# clock14.net
KiCad netlist of a schematic drawn in EAGLE
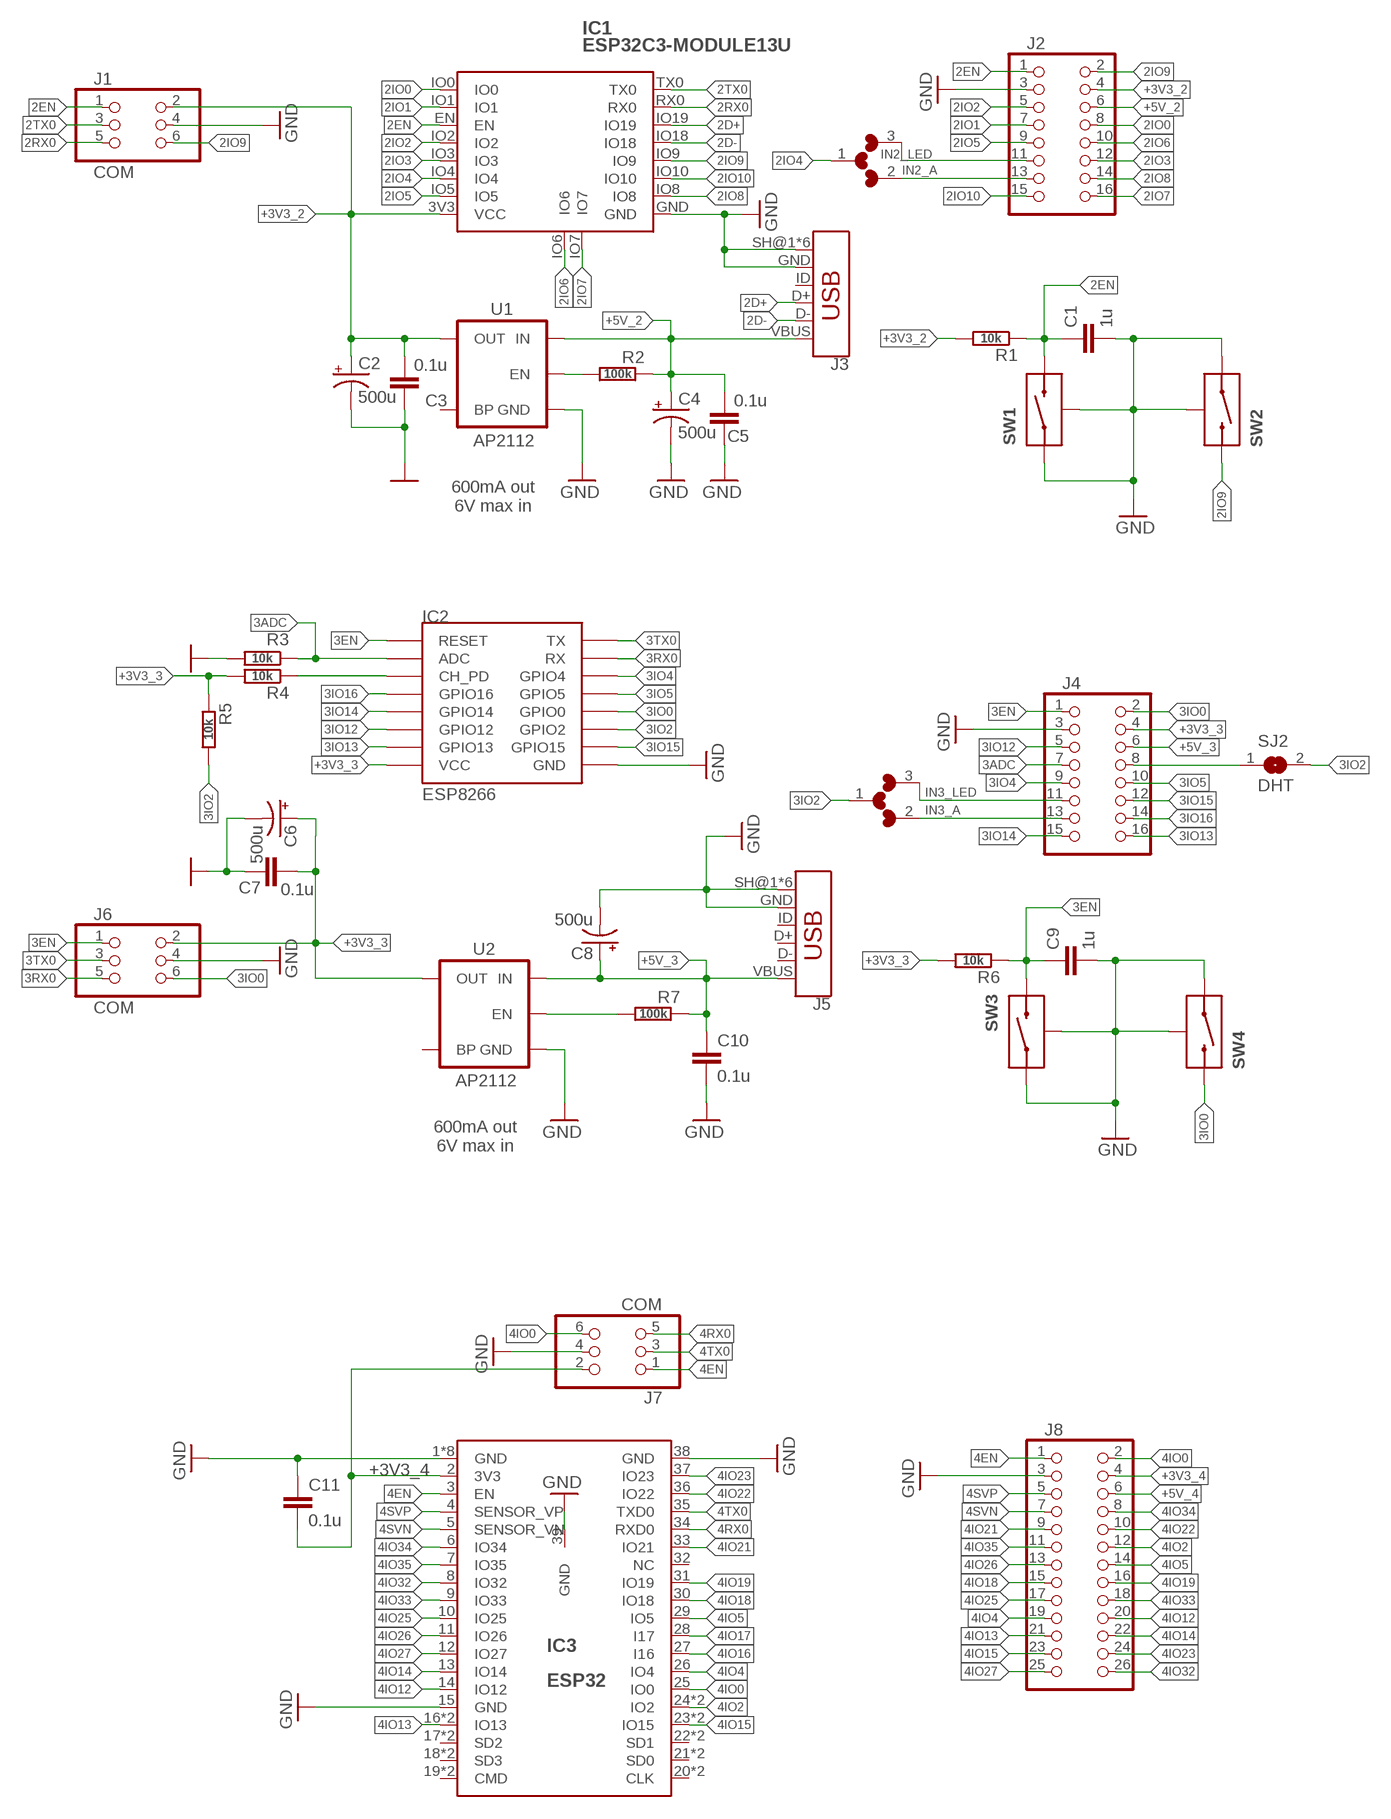
[diagram p0: schematic, sheet 1, part 1 of 2]
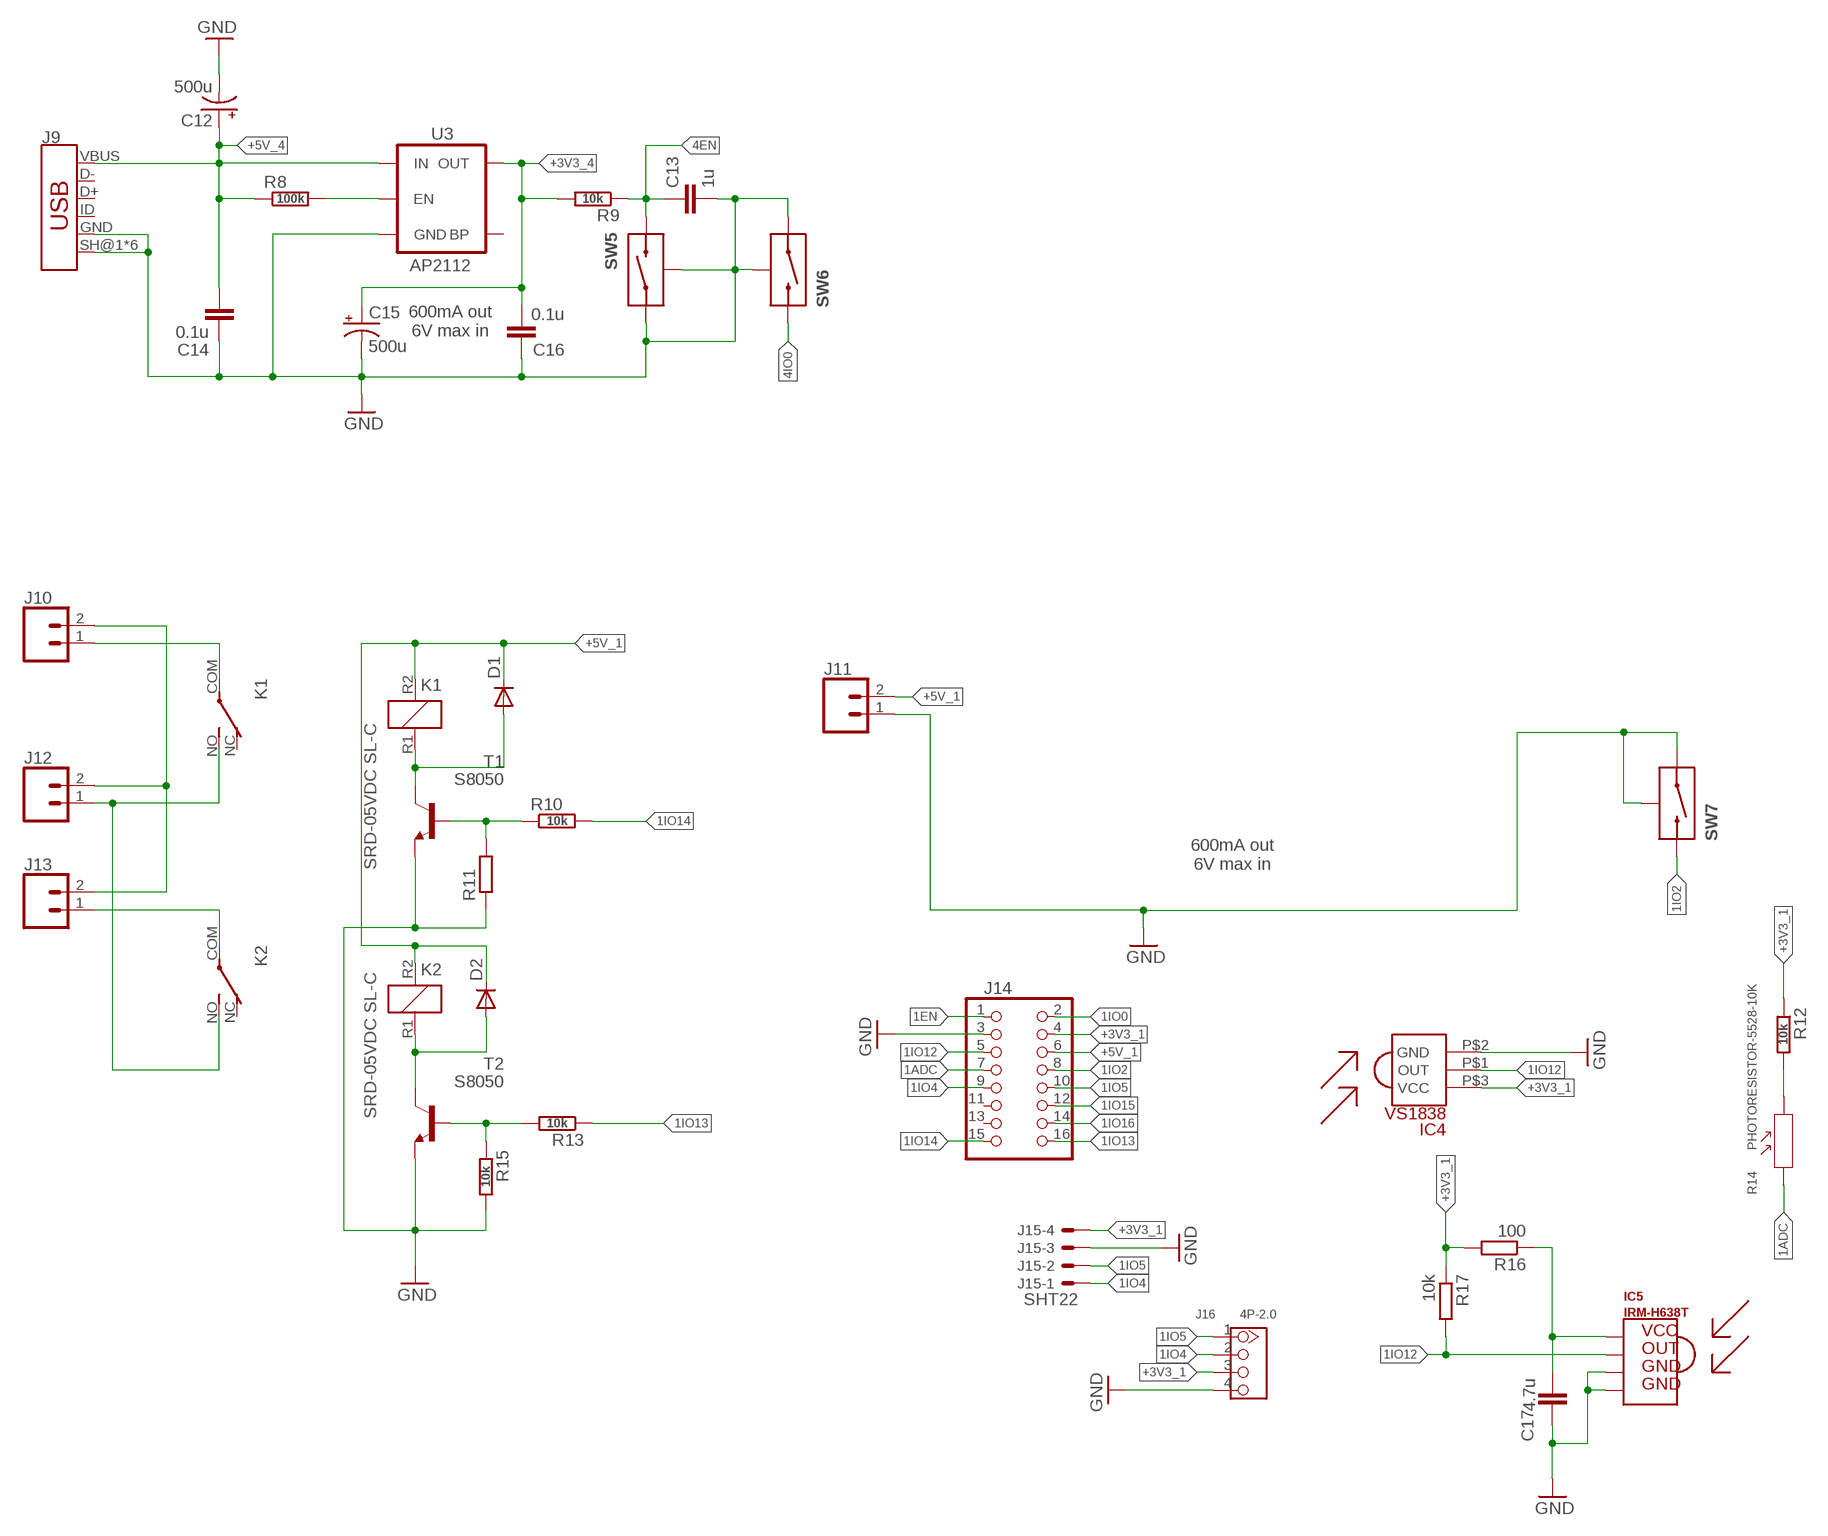
[diagram p1: schematic, sheet 1, part 2 of 2]

(export (version "E")
  (design (tool "Eeschema 10.0.6"))
  (components
    (comp (ref "C1")
      (value "1u")
      (footprint "eagle-import:0603-CAP")
      (libsource (lib "eagle-import") (part "CAP0603-CAP"))
    )
    (comp (ref "C2")
      (value "500u")
      (footprint "eagle-import:CPOL-RADIAL-100UF-25V")
      (libsource (lib "eagle-import") (part "CAP_POLPTH1"))
    )
    (comp (ref "C3")
      (value "0.1u")
      (footprint "eagle-import:0603-CAP")
      (libsource (lib "eagle-import") (part "CAP0603-CAP"))
    )
    (comp (ref "C4")
      (value "500u")
      (footprint "eagle-import:CPOL-RADIAL-100UF-25V")
      (libsource (lib "eagle-import") (part "CAP_POLPTH1"))
    )
    (comp (ref "C5")
      (value "0.1u")
      (footprint "eagle-import:0603-CAP")
      (libsource (lib "eagle-import") (part "CAP0603-CAP"))
    )
    (comp (ref "C6")
      (value "500u")
      (footprint "eagle-import:CPOL-RADIAL-100UF-25V")
      (libsource (lib "eagle-import") (part "CAP_POLPTH1"))
    )
    (comp (ref "C7")
      (value "0.1u")
      (footprint "eagle-import:0603-CAP")
      (libsource (lib "eagle-import") (part "CAP0603-CAP"))
    )
    (comp (ref "C8")
      (value "500u")
      (footprint "eagle-import:CPOL-RADIAL-100UF-25V")
      (libsource (lib "eagle-import") (part "CAP_POLPTH1"))
    )
    (comp (ref "C9")
      (value "1u")
      (footprint "eagle-import:0603-CAP")
      (libsource (lib "eagle-import") (part "CAP0603-CAP"))
    )
    (comp (ref "C10")
      (value "0.1u")
      (footprint "eagle-import:0603-CAP")
      (libsource (lib "eagle-import") (part "CAP0603-CAP"))
    )
    (comp (ref "C11")
      (value "0.1u")
      (footprint "eagle-import:0603-CAP")
      (libsource (lib "eagle-import") (part "CAP0603-CAP"))
    )
    (comp (ref "C12")
      (value "500u")
      (footprint "eagle-import:CPOL-RADIAL-100UF-25V")
      (libsource (lib "eagle-import") (part "CAP_POLPTH1"))
    )
    (comp (ref "C13")
      (value "1u")
      (footprint "eagle-import:0603-CAP")
      (libsource (lib "eagle-import") (part "CAP0603-CAP"))
    )
    (comp (ref "C14")
      (value "0.1u")
      (footprint "eagle-import:0603-CAP")
      (libsource (lib "eagle-import") (part "CAP0603-CAP"))
    )
    (comp (ref "C15")
      (value "500u")
      (footprint "eagle-import:CPOL-RADIAL-100UF-25V")
      (libsource (lib "eagle-import") (part "CAP_POLPTH1"))
    )
    (comp (ref "C16")
      (value "0.1u")
      (footprint "eagle-import:0603-CAP")
      (libsource (lib "eagle-import") (part "CAP0603-CAP"))
    )
    (comp (ref "C17")
      (value "4.7u")
      (footprint "eagle-import:0603-CAP")
      (libsource (lib "eagle-import") (part "CAP0603-CAP"))
    )
    (comp (ref "D1")
      (value "DIODE-SOD123")
      (footprint "eagle-import:SOD123")
      (libsource (lib "eagle-import") (part "DIODE-SOD123"))
    )
    (comp (ref "D2")
      (value "DIODE-SOD123")
      (footprint "eagle-import:SOD123")
      (libsource (lib "eagle-import") (part "DIODE-SOD123"))
    )
    (comp (ref "IC1")
      (value "ESP32C3-MODULE13U")
      (footprint "eagle-import:ESP32C3-13U")
      (libsource (lib "eagle-import") (part "ESP32C3-MODULE13U"))
    )
    (comp (ref "IC2")
      (value "ESP8266")
      (footprint "eagle-import:ESP12-SMD")
      (libsource (lib "eagle-import") (part "ESP12SMD"))
    )
    (comp (ref "IC3")
      (value "ESP32")
      (footprint "eagle-import:ESP32-WROOVER_WROOM")
      (libsource (lib "eagle-import") (part "ESP32-MODULEDUAL"))
    )
    (comp (ref "IC4")
      (value "VS1838")
      (footprint "eagle-import:IR")
      (libsource (lib "eagle-import") (part "VS1838"))
    )
    (comp (ref "IC5")
      (value "IRM-H638T")
      (footprint "eagle-import:IRM-H638T")
      (libsource (lib "eagle-import") (part "IRM-H638T"))
    )
    (comp (ref "J1")
      (value "COM")
      (footprint "eagle-import:2X03_SMT")
      (libsource (lib "eagle-import") (part "HEADER-2X3SMT"))
    )
    (comp (ref "J2")
      (value "HEADER-2X8")
      (footprint "eagle-import:2X8")
      (libsource (lib "eagle-import") (part "HEADER-2X8"))
    )
    (comp (ref "J3")
      (value "USB_MICRO-BFEMALE_SMT_")
      (footprint "eagle-import:USB-B-MICRO-SMD_MY")
      (libsource (lib "eagle-import") (part "USB_MICRO-BFEMALE_SMT_"))
    )
    (comp (ref "J4")
      (value "HEADER-2X8")
      (footprint "eagle-import:2X8")
      (libsource (lib "eagle-import") (part "HEADER-2X8"))
    )
    (comp (ref "J5")
      (value "USB_MICRO-BFEMALE_SMT_")
      (footprint "eagle-import:USB-B-MICRO-SMD_MY")
      (libsource (lib "eagle-import") (part "USB_MICRO-BFEMALE_SMT_"))
    )
    (comp (ref "J6")
      (value "COM")
      (footprint "eagle-import:2X03_SMT")
      (libsource (lib "eagle-import") (part "HEADER-2X3SMT"))
    )
    (comp (ref "J7")
      (value "COM")
      (footprint "eagle-import:2X03_SMT")
      (libsource (lib "eagle-import") (part "HEADER-2X3SMT"))
    )
    (comp (ref "J8")
      (value "HEADER-2X13")
      (footprint "eagle-import:2X13")
      (libsource (lib "eagle-import") (part "HEADER-2X13"))
    )
    (comp (ref "J9")
      (value "USB_MICRO-BFEMALE_SMT_")
      (footprint "eagle-import:USB-B-MICRO-SMD_MY")
      (libsource (lib "eagle-import") (part "USB_MICRO-BFEMALE_SMT_"))
    )
    (comp (ref "J10")
      (value "CONN_02")
      (footprint "eagle-import:1X02")
      (libsource (lib "eagle-import") (part "CONN_02"))
    )
    (comp (ref "J11")
      (value "CONN_02")
      (footprint "eagle-import:1X02")
      (libsource (lib "eagle-import") (part "CONN_02"))
    )
    (comp (ref "J12")
      (value "CONN_02")
      (footprint "eagle-import:1X02")
      (libsource (lib "eagle-import") (part "CONN_02"))
    )
    (comp (ref "J13")
      (value "CONN_02")
      (footprint "eagle-import:1X02")
      (libsource (lib "eagle-import") (part "CONN_02"))
    )
    (comp (ref "J14")
      (value "HEADER-2X8")
      (footprint "eagle-import:2X8")
      (libsource (lib "eagle-import") (part "HEADER-2X8"))
    )
    (comp (ref "J15")
      (value "SHT22")
      (footprint "eagle-import:70543-04")
      (libsource (lib "eagle-import") (part "C-GRID-04-70543"))
    )
    (comp (ref "J16")
      (value "4P-2.0")
      (footprint "eagle-import:HW4-2.0")
      (libsource (lib "eagle-import") (part "GROVE-CONNECTOR-DIP(4P-2.0)"))
    )
    (comp (ref "K1")
      (value "SRD-05VDC SL-C")
      (footprint "eagle-import:SL-C")
      (fields (field (name "MF") "AROMAT/ MATSUSHITA") (field (name "MPN") "CB1A-P-12V"))
      (libsource (lib "eagle-import") (part "CB1A-P-12V"))
    )
    (comp (ref "K2")
      (value "SRD-05VDC SL-C")
      (footprint "eagle-import:SL-C")
      (fields (field (name "MF") "AROMAT/ MATSUSHITA") (field (name "MPN") "CB1A-P-12V"))
      (libsource (lib "eagle-import") (part "CB1A-P-12V"))
    )
    (comp (ref "R1")
      (value "10k")
      (footprint "eagle-import:R0603")
      (libsource (lib "eagle-import") (part "R-EU_R0603"))
    )
    (comp (ref "R2")
      (value "100k")
      (footprint "eagle-import:R0603")
      (libsource (lib "eagle-import") (part "R-EU_R0603"))
    )
    (comp (ref "R3")
      (value "10k")
      (footprint "eagle-import:R0603")
      (libsource (lib "eagle-import") (part "R-EU_R0603"))
    )
    (comp (ref "R4")
      (value "10k")
      (footprint "eagle-import:R0603")
      (libsource (lib "eagle-import") (part "R-EU_R0603"))
    )
    (comp (ref "R5")
      (value "10k")
      (footprint "eagle-import:R0603")
      (libsource (lib "eagle-import") (part "R-EU_R0603"))
    )
    (comp (ref "R6")
      (value "10k")
      (footprint "eagle-import:R0603")
      (libsource (lib "eagle-import") (part "R-EU_R0603"))
    )
    (comp (ref "R7")
      (value "100k")
      (footprint "eagle-import:R0603")
      (libsource (lib "eagle-import") (part "R-EU_R0603"))
    )
    (comp (ref "R8")
      (value "100k")
      (footprint "eagle-import:R0603")
      (libsource (lib "eagle-import") (part "R-EU_R0603"))
    )
    (comp (ref "R9")
      (value "10k")
      (footprint "eagle-import:R0603")
      (libsource (lib "eagle-import") (part "R-EU_R0603"))
    )
    (comp (ref "R10")
      (value "10k")
      (footprint "eagle-import:R0603")
      (libsource (lib "eagle-import") (part "R-EU_R0603"))
    )
    (comp (ref "R11")
      (value "R-EU_R0603")
      (footprint "eagle-import:R0603")
      (libsource (lib "eagle-import") (part "R-EU_R0603"))
    )
    (comp (ref "R12")
      (value "10k")
      (footprint "eagle-import:R0603")
      (libsource (lib "eagle-import") (part "R-EU_R0603"))
    )
    (comp (ref "R13")
      (value "10k")
      (footprint "eagle-import:R0603")
      (libsource (lib "eagle-import") (part "R-EU_R0603"))
    )
    (comp (ref "R14")
      (value "PHOTORESISTOR-5528-10K")
      (footprint "eagle-import:SNR2-3.0")
      (libsource (lib "eagle-import") (part "PHOTORESISTOR-5528-10K(2P-5.0X4.2MM)"))
    )
    (comp (ref "R15")
      (value "10k")
      (footprint "eagle-import:R0603")
      (libsource (lib "eagle-import") (part "R-EU_R0603"))
    )
    (comp (ref "R16")
      (value "100")
      (footprint "eagle-import:R0603")
      (libsource (lib "eagle-import") (part "R-EU_R0603"))
    )
    (comp (ref "R17")
      (value "10k")
      (footprint "eagle-import:R0603")
      (libsource (lib "eagle-import") (part "R-EU_R0603"))
    )
    (comp (ref "SJ1")
      (value "L/W")
      (footprint "eagle-import:MICROBUILDER_SOLDERJUMPER_ARROW_NOPASTE_3")
      (libsource (lib "eagle-import") (part "MICROBUILDER_SOLDERJUMPER3"))
    )
    (comp (ref "SJ2")
      (value "DHT")
      (footprint "eagle-import:MICROBUILDER_SOLDERJUMPER_ARROW_NOPASTE")
      (libsource (lib "eagle-import") (part "MICROBUILDER_SOLDERJUMPER"))
    )
    (comp (ref "SJ3")
      (value "L/W")
      (footprint "eagle-import:MICROBUILDER_SOLDERJUMPER_ARROW_NOPASTE_3")
      (libsource (lib "eagle-import") (part "MICROBUILDER_SOLDERJUMPER3"))
    )
    (comp (ref "SW1")
      (value "RST")
      (footprint "eagle-import:MICROPUSH-BUT_TOP")
      (libsource (lib "eagle-import") (part "MICROSWITCH-BUTTON"))
    )
    (comp (ref "SW2")
      (value "PRG")
      (footprint "eagle-import:MICROPUSH-BUT_TOP")
      (libsource (lib "eagle-import") (part "MICROSWITCH-BUTTON"))
    )
    (comp (ref "SW3")
      (value "RST")
      (footprint "eagle-import:MICROPUSH-BUT_TOP")
      (libsource (lib "eagle-import") (part "MICROSWITCH-BUTTON"))
    )
    (comp (ref "SW4")
      (value "PRG")
      (footprint "eagle-import:MICROPUSH-BUT_TOP")
      (libsource (lib "eagle-import") (part "MICROSWITCH-BUTTON"))
    )
    (comp (ref "SW5")
      (value "RST")
      (footprint "eagle-import:MICROPUSH-BUT_TOP")
      (libsource (lib "eagle-import") (part "MICROSWITCH-BUTTON"))
    )
    (comp (ref "SW6")
      (value "PRG")
      (footprint "eagle-import:MICROPUSH-BUT_TOP")
      (libsource (lib "eagle-import") (part "MICROSWITCH-BUTTON"))
    )
    (comp (ref "SW7")
      (value "PRG")
      (footprint "eagle-import:MICROPUSH-BUT_TOP")
      (libsource (lib "eagle-import") (part "MICROSWITCH-BUTTON"))
    )
    (comp (ref "T1")
      (value "S8050")
      (footprint "eagle-import:SOT23-EBC")
      (libsource (lib "eagle-import") (part "-NPN-SOT23-EBC"))
    )
    (comp (ref "T2")
      (value "S8050")
      (footprint "eagle-import:SOT23-EBC")
      (libsource (lib "eagle-import") (part "-NPN-SOT23-EBC"))
    )
    (comp (ref "U1")
      (value "AP2112")
      (footprint "eagle-import:SOT23-5")
      (libsource (lib "eagle-import") (part "V_REG_LDOSMD"))
    )
    (comp (ref "U2")
      (value "AP2112")
      (footprint "eagle-import:SOT23-5")
      (libsource (lib "eagle-import") (part "V_REG_LDOSMD"))
    )
    (comp (ref "U3")
      (value "AP2112")
      (footprint "eagle-import:SOT23-5")
      (libsource (lib "eagle-import") (part "V_REG_LDOSMD"))
    )
  )
  (nets
    (net (code "1") (name "+3V3_1") (class "Default")
      (node (ref "IC4") (pin "P$3") (pinfunction "VCC_P$3") (pintype "bidirectional"))
      (node (ref "J14") (pin "4") (pinfunction "4_4") (pintype "passive"))
      (node (ref "J15") (pin "4") (pinfunction "S_4") (pintype "passive"))
      (node (ref "J16") (pin "3") (pinfunction "3_3") (pintype "bidirectional"))
      (node (ref "R12") (pin "1") (pinfunction "1_1") (pintype "passive"))
      (node (ref "R16") (pin "2") (pinfunction "2_2") (pintype "passive"))
      (node (ref "R17") (pin "1") (pinfunction "1_1") (pintype "passive"))
    )
    (net (code "2") (name "+3V3_2") (class "Default")
      (node (ref "C2") (pin "1") (pinfunction "+_1") (pintype "passive"))
      (node (ref "C3") (pin "2") (pinfunction "2_2") (pintype "passive"))
      (node (ref "IC1") (pin "3V3") (pinfunction "VCC_3V3") (pintype "power_in"))
      (node (ref "J1") (pin "2") (pinfunction "2_2") (pintype "passive"))
      (node (ref "J2") (pin "4") (pinfunction "4_4") (pintype "passive"))
      (node (ref "R1") (pin "2") (pinfunction "2_2") (pintype "passive"))
      (node (ref "U1") (pin "5") (pinfunction "OUT_5") (pintype "passive"))
    )
    (net (code "3") (name "+3V3_3") (class "Default")
      (node (ref "C6") (pin "1") (pinfunction "+_1") (pintype "passive"))
      (node (ref "C7") (pin "2") (pinfunction "2_2") (pintype "passive"))
      (node (ref "IC2") (pin "VCC") (pinfunction "VCC_VCC") (pintype "bidirectional"))
      (node (ref "J4") (pin "4") (pinfunction "4_4") (pintype "passive"))
      (node (ref "J6") (pin "2") (pinfunction "2_2") (pintype "passive"))
      (node (ref "R4") (pin "2") (pinfunction "2_2") (pintype "passive"))
      (node (ref "R5") (pin "1") (pinfunction "1_1") (pintype "passive"))
      (node (ref "R6") (pin "2") (pinfunction "2_2") (pintype "passive"))
      (node (ref "U2") (pin "5") (pinfunction "OUT_5") (pintype "passive"))
    )
    (net (code "4") (name "+3V3_4") (class "Default")
      (node (ref "C11") (pin "2") (pinfunction "2_2") (pintype "passive"))
      (node (ref "C15") (pin "1") (pinfunction "+_1") (pintype "passive"))
      (node (ref "C16") (pin "2") (pinfunction "2_2") (pintype "passive"))
      (node (ref "IC3") (pin "2") (pinfunction "3V3_2") (pintype "power_in"))
      (node (ref "J7") (pin "2") (pinfunction "2_2") (pintype "passive"))
      (node (ref "J8") (pin "4") (pinfunction "4_4") (pintype "passive"))
      (node (ref "R9") (pin "2") (pinfunction "2_2") (pintype "passive"))
      (node (ref "U3") (pin "5") (pinfunction "OUT_5") (pintype "passive"))
    )
    (net (code "5") (name "+5V_1") (class "Default")
      (node (ref "D1") (pin "C") (pinfunction "C_C") (pintype "passive"))
      (node (ref "D2") (pin "C") (pinfunction "C_C") (pintype "passive"))
      (node (ref "J11") (pin "2") (pinfunction "2_2") (pintype "passive"))
      (node (ref "J14") (pin "6") (pinfunction "6_6") (pintype "passive"))
      (node (ref "K1") (pin "R2") (pinfunction "2_R2") (pintype "passive"))
      (node (ref "K2") (pin "R2") (pinfunction "2_R2") (pintype "passive"))
    )
    (net (code "6") (name "+5V_2") (class "Default")
      (node (ref "C4") (pin "1") (pinfunction "+_1") (pintype "passive"))
      (node (ref "C5") (pin "2") (pinfunction "2_2") (pintype "passive"))
      (node (ref "J2") (pin "6") (pinfunction "6_6") (pintype "passive"))
      (node (ref "J3") (pin "VBUS") (pinfunction "VBUS_VBUS") (pintype "power_in"))
      (node (ref "R2") (pin "1") (pinfunction "1_1") (pintype "passive"))
      (node (ref "U1") (pin "1") (pinfunction "IN_1") (pintype "input"))
    )
    (net (code "7") (name "+5V_3") (class "Default")
      (node (ref "C10") (pin "1") (pinfunction "1_1") (pintype "passive"))
      (node (ref "C8") (pin "1") (pinfunction "+_1") (pintype "passive"))
      (node (ref "J4") (pin "6") (pinfunction "6_6") (pintype "passive"))
      (node (ref "J5") (pin "VBUS") (pinfunction "VBUS_VBUS") (pintype "power_in"))
      (node (ref "R7") (pin "1") (pinfunction "1_1") (pintype "passive"))
      (node (ref "U2") (pin "1") (pinfunction "IN_1") (pintype "input"))
    )
    (net (code "8") (name "+5V_4") (class "Default")
      (node (ref "C12") (pin "1") (pinfunction "+_1") (pintype "passive"))
      (node (ref "C14") (pin "1") (pinfunction "1_1") (pintype "passive"))
      (node (ref "J8") (pin "6") (pinfunction "6_6") (pintype "passive"))
      (node (ref "J9") (pin "VBUS") (pinfunction "VBUS_VBUS") (pintype "power_in"))
      (node (ref "R8") (pin "1") (pinfunction "1_1") (pintype "passive"))
      (node (ref "U3") (pin "1") (pinfunction "IN_1") (pintype "input"))
    )
    (net (code "9") (name "/IN2_A") (class "Default")
      (node (ref "J2") (pin "13") (pinfunction "13_13") (pintype "passive"))
      (node (ref "SJ1") (pin "2") (pinfunction "2_2") (pintype "passive"))
    )
    (net (code "10") (name "/IN2_LED") (class "Default")
      (node (ref "J2") (pin "11") (pinfunction "11_11") (pintype "passive"))
      (node (ref "SJ1") (pin "3") (pinfunction "3_3") (pintype "passive"))
    )
    (net (code "11") (name "/IN3_A") (class "Default")
      (node (ref "J4") (pin "13") (pinfunction "13_13") (pintype "passive"))
      (node (ref "SJ3") (pin "2") (pinfunction "2_2") (pintype "passive"))
    )
    (net (code "12") (name "/IN3_LED") (class "Default")
      (node (ref "J4") (pin "11") (pinfunction "11_11") (pintype "passive"))
      (node (ref "SJ3") (pin "3") (pinfunction "3_3") (pintype "passive"))
    )
    (net (code "13") (name "1ADC") (class "Default")
      (node (ref "J14") (pin "7") (pinfunction "7_7") (pintype "passive"))
      (node (ref "R14") (pin "1") (pinfunction "P$1_1") (pintype "bidirectional"))
    )
    (net (code "14") (name "1EN") (class "Default")
      (node (ref "J14") (pin "1") (pinfunction "1_1") (pintype "passive"))
    )
    (net (code "15") (name "1IO0") (class "Default")
      (node (ref "J14") (pin "2") (pinfunction "2_2") (pintype "passive"))
    )
    (net (code "16") (name "1IO2") (class "Default")
      (node (ref "J14") (pin "8") (pinfunction "8_8") (pintype "passive"))
      (node (ref "SW7") (pin "B") (pinfunction "B_B") (pintype "passive"))
    )
    (net (code "17") (name "1IO4") (class "Default")
      (node (ref "J14") (pin "9") (pinfunction "9_9") (pintype "passive"))
      (node (ref "J15") (pin "1") (pinfunction "S_1") (pintype "passive"))
      (node (ref "J16") (pin "2") (pinfunction "2_2") (pintype "bidirectional"))
    )
    (net (code "18") (name "1IO5") (class "Default")
      (node (ref "J14") (pin "10") (pinfunction "10_10") (pintype "passive"))
      (node (ref "J15") (pin "2") (pinfunction "S_2") (pintype "passive"))
      (node (ref "J16") (pin "1") (pinfunction "1_1") (pintype "bidirectional"))
    )
    (net (code "19") (name "1IO12") (class "Default")
      (node (ref "IC4") (pin "P$1") (pinfunction "OUT_P$1") (pintype "bidirectional"))
      (node (ref "IC5") (pin "OUT") (pinfunction "OUT_OUT") (pintype "output"))
      (node (ref "J14") (pin "5") (pinfunction "5_5") (pintype "passive"))
      (node (ref "R17") (pin "2") (pinfunction "2_2") (pintype "passive"))
    )
    (net (code "20") (name "1IO13") (class "Default")
      (node (ref "J14") (pin "16") (pinfunction "16_16") (pintype "passive"))
      (node (ref "R13") (pin "1") (pinfunction "1_1") (pintype "passive"))
    )
    (net (code "21") (name "1IO14") (class "Default")
      (node (ref "J14") (pin "15") (pinfunction "15_15") (pintype "passive"))
      (node (ref "R10") (pin "2") (pinfunction "2_2") (pintype "passive"))
    )
    (net (code "22") (name "1IO15") (class "Default")
      (node (ref "J14") (pin "12") (pinfunction "12_12") (pintype "passive"))
    )
    (net (code "23") (name "1IO16") (class "Default")
      (node (ref "J14") (pin "14") (pinfunction "14_14") (pintype "passive"))
    )
    (net (code "24") (name "2D+") (class "Default")
      (node (ref "IC1") (pin "IO19") (pinfunction "IO19_IO19") (pintype "bidirectional"))
      (node (ref "J3") (pin "D+") (pinfunction "D+_D+") (pintype "bidirectional"))
    )
    (net (code "25") (name "2D-") (class "Default")
      (node (ref "IC1") (pin "IO18") (pinfunction "IO18_IO18") (pintype "bidirectional"))
      (node (ref "J3") (pin "D-") (pinfunction "D-_D-") (pintype "bidirectional"))
    )
    (net (code "26") (name "2EN") (class "Default")
      (node (ref "C1") (pin "1") (pinfunction "1_1") (pintype "passive"))
      (node (ref "IC1") (pin "EN") (pinfunction "EN_EN") (pintype "bidirectional"))
      (node (ref "J1") (pin "1") (pinfunction "1_1") (pintype "passive"))
      (node (ref "J2") (pin "1") (pinfunction "1_1") (pintype "passive"))
      (node (ref "R1") (pin "1") (pinfunction "1_1") (pintype "passive"))
      (node (ref "SW1") (pin "B") (pinfunction "B_B") (pintype "passive"))
    )
    (net (code "27") (name "2IO0") (class "Default")
      (node (ref "IC1") (pin "IO0") (pinfunction "IO0_IO0") (pintype "bidirectional"))
      (node (ref "J2") (pin "8") (pinfunction "8_8") (pintype "passive"))
    )
    (net (code "28") (name "2IO1") (class "Default")
      (node (ref "IC1") (pin "IO1") (pinfunction "IO1_IO1") (pintype "bidirectional"))
      (node (ref "J2") (pin "7") (pinfunction "7_7") (pintype "passive"))
    )
    (net (code "29") (name "2IO2") (class "Default")
      (node (ref "IC1") (pin "IO2") (pinfunction "IO2_IO2") (pintype "bidirectional"))
      (node (ref "J2") (pin "5") (pinfunction "5_5") (pintype "passive"))
    )
    (net (code "30") (name "2IO3") (class "Default")
      (node (ref "IC1") (pin "IO3") (pinfunction "IO3_IO3") (pintype "bidirectional"))
      (node (ref "J2") (pin "12") (pinfunction "12_12") (pintype "passive"))
    )
    (net (code "31") (name "2IO4") (class "Default")
      (node (ref "IC1") (pin "IO4") (pinfunction "IO4_IO4") (pintype "bidirectional"))
      (node (ref "SJ1") (pin "1") (pinfunction "1_1") (pintype "passive"))
    )
    (net (code "32") (name "2IO5") (class "Default")
      (node (ref "IC1") (pin "IO5") (pinfunction "IO5_IO5") (pintype "bidirectional"))
      (node (ref "J2") (pin "9") (pinfunction "9_9") (pintype "passive"))
    )
    (net (code "33") (name "2IO6") (class "Default")
      (node (ref "IC1") (pin "IO6") (pinfunction "IO6_IO6") (pintype "bidirectional"))
      (node (ref "J2") (pin "10") (pinfunction "10_10") (pintype "passive"))
    )
    (net (code "34") (name "2IO7") (class "Default")
      (node (ref "IC1") (pin "IO7") (pinfunction "IO7_IO7") (pintype "bidirectional"))
      (node (ref "J2") (pin "16") (pinfunction "16_16") (pintype "passive"))
    )
    (net (code "35") (name "2IO8") (class "Default")
      (node (ref "IC1") (pin "IO8") (pinfunction "IO8_IO8") (pintype "bidirectional"))
      (node (ref "J2") (pin "14") (pinfunction "14_14") (pintype "passive"))
    )
    (net (code "36") (name "2IO9") (class "Default")
      (node (ref "IC1") (pin "IO9") (pinfunction "IO9_IO9") (pintype "bidirectional"))
      (node (ref "J1") (pin "6") (pinfunction "6_6") (pintype "passive"))
      (node (ref "J2") (pin "2") (pinfunction "2_2") (pintype "passive"))
      (node (ref "SW2") (pin "B") (pinfunction "B_B") (pintype "passive"))
    )
    (net (code "37") (name "2IO10") (class "Default")
      (node (ref "IC1") (pin "IO10") (pinfunction "IO10_IO10") (pintype "bidirectional"))
      (node (ref "J2") (pin "15") (pinfunction "15_15") (pintype "passive"))
    )
    (net (code "38") (name "2RX0") (class "Default")
      (node (ref "IC1") (pin "RX0") (pinfunction "RX0_RX0") (pintype "input"))
      (node (ref "J1") (pin "5") (pinfunction "5_5") (pintype "passive"))
    )
    (net (code "39") (name "2TX0") (class "Default")
      (node (ref "IC1") (pin "TX0") (pinfunction "TX0_TX0") (pintype "output"))
      (node (ref "J1") (pin "3") (pinfunction "3_3") (pintype "passive"))
    )
    (net (code "40") (name "3ADC") (class "Default")
      (node (ref "IC2") (pin "ADC") (pinfunction "ADC_ADC") (pintype "bidirectional"))
      (node (ref "J4") (pin "7") (pinfunction "7_7") (pintype "passive"))
      (node (ref "R3") (pin "1") (pinfunction "1_1") (pintype "passive"))
    )
    (net (code "41") (name "3EN") (class "Default")
      (node (ref "C9") (pin "1") (pinfunction "1_1") (pintype "passive"))
      (node (ref "IC2") (pin "RESET") (pinfunction "RESET_RESET") (pintype "bidirectional"))
      (node (ref "J4") (pin "1") (pinfunction "1_1") (pintype "passive"))
      (node (ref "J6") (pin "1") (pinfunction "1_1") (pintype "passive"))
      (node (ref "R6") (pin "1") (pinfunction "1_1") (pintype "passive"))
      (node (ref "SW3") (pin "B") (pinfunction "B_B") (pintype "passive"))
    )
    (net (code "42") (name "3IO0") (class "Default")
      (node (ref "IC2") (pin "GPIO0") (pinfunction "GPIO0_GPIO0") (pintype "bidirectional"))
      (node (ref "J4") (pin "2") (pinfunction "2_2") (pintype "passive"))
      (node (ref "J6") (pin "6") (pinfunction "6_6") (pintype "passive"))
      (node (ref "SW4") (pin "B") (pinfunction "B_B") (pintype "passive"))
    )
    (net (code "43") (name "3IO2") (class "Default")
      (node (ref "IC2") (pin "GPIO2") (pinfunction "GPIO2_GPIO2") (pintype "bidirectional"))
      (node (ref "R5") (pin "2") (pinfunction "2_2") (pintype "passive"))
      (node (ref "SJ2") (pin "2") (pinfunction "2_2") (pintype "passive"))
      (node (ref "SJ3") (pin "1") (pinfunction "1_1") (pintype "passive"))
    )
    (net (code "44") (name "3IO4") (class "Default")
      (node (ref "IC2") (pin "GPIO4") (pinfunction "GPIO4_GPIO4") (pintype "bidirectional"))
      (node (ref "J4") (pin "9") (pinfunction "9_9") (pintype "passive"))
    )
    (net (code "45") (name "3IO5") (class "Default")
      (node (ref "IC2") (pin "GPIO5") (pinfunction "GPIO5_GPIO5") (pintype "bidirectional"))
      (node (ref "J4") (pin "10") (pinfunction "10_10") (pintype "passive"))
    )
    (net (code "46") (name "3IO12") (class "Default")
      (node (ref "IC2") (pin "GPIO12") (pinfunction "GPIO12_GPIO12") (pintype "bidirectional"))
      (node (ref "J4") (pin "5") (pinfunction "5_5") (pintype "passive"))
    )
    (net (code "47") (name "3IO13") (class "Default")
      (node (ref "IC2") (pin "GPIO13") (pinfunction "GPIO13_GPIO13") (pintype "bidirectional"))
      (node (ref "J4") (pin "16") (pinfunction "16_16") (pintype "passive"))
    )
    (net (code "48") (name "3IO14") (class "Default")
      (node (ref "IC2") (pin "GPIO14") (pinfunction "GPIO14_GPIO14") (pintype "bidirectional"))
      (node (ref "J4") (pin "15") (pinfunction "15_15") (pintype "passive"))
    )
    (net (code "49") (name "3IO15") (class "Default")
      (node (ref "IC2") (pin "GPIO15") (pinfunction "GPIO15_GPIO15") (pintype "bidirectional"))
      (node (ref "J4") (pin "12") (pinfunction "12_12") (pintype "passive"))
    )
    (net (code "50") (name "3IO16") (class "Default")
      (node (ref "IC2") (pin "GPIO16") (pinfunction "GPIO16_GPIO16") (pintype "bidirectional"))
      (node (ref "J4") (pin "14") (pinfunction "14_14") (pintype "passive"))
    )
    (net (code "51") (name "3RX0") (class "Default")
      (node (ref "IC2") (pin "RXD0") (pinfunction "RX_RXD0") (pintype "bidirectional"))
      (node (ref "J6") (pin "5") (pinfunction "5_5") (pintype "passive"))
    )
    (net (code "52") (name "3TX0") (class "Default")
      (node (ref "IC2") (pin "TXD0") (pinfunction "TX_TXD0") (pintype "bidirectional"))
      (node (ref "J6") (pin "3") (pinfunction "3_3") (pintype "passive"))
    )
    (net (code "53") (name "4EN") (class "Default")
      (node (ref "C13") (pin "1") (pinfunction "1_1") (pintype "passive"))
      (node (ref "IC3") (pin "3") (pinfunction "EN_3") (pintype "input"))
      (node (ref "J7") (pin "1") (pinfunction "1_1") (pintype "passive"))
      (node (ref "J8") (pin "1") (pinfunction "1_1") (pintype "passive"))
      (node (ref "R9") (pin "1") (pinfunction "1_1") (pintype "passive"))
      (node (ref "SW5") (pin "B") (pinfunction "B_B") (pintype "passive"))
    )
    (net (code "54") (name "4IO0") (class "Default")
      (node (ref "IC3") (pin "25") (pinfunction "IO0_25") (pintype "bidirectional"))
      (node (ref "J7") (pin "6") (pinfunction "6_6") (pintype "passive"))
      (node (ref "J8") (pin "2") (pinfunction "2_2") (pintype "passive"))
      (node (ref "SW6") (pin "B") (pinfunction "B_B") (pintype "passive"))
    )
    (net (code "55") (name "4IO2") (class "Default")
      (node (ref "IC3") (pin "24") (pinfunction "IO2_24") (pintype "bidirectional"))
      (node (ref "IC3") (pin "48") (pinfunction "IO2_48") (pintype "bidirectional"))
      (node (ref "J8") (pin "12") (pinfunction "12_12") (pintype "passive"))
    )
    (net (code "56") (name "4IO4") (class "Default")
      (node (ref "IC3") (pin "26") (pinfunction "IO4_26") (pintype "bidirectional"))
      (node (ref "J8") (pin "19") (pinfunction "19_19") (pintype "passive"))
    )
    (net (code "57") (name "4IO5") (class "Default")
      (node (ref "IC3") (pin "29") (pinfunction "IO5_29") (pintype "bidirectional"))
      (node (ref "J8") (pin "14") (pinfunction "14_14") (pintype "passive"))
    )
    (net (code "58") (name "4IO12") (class "Default")
      (node (ref "IC3") (pin "14") (pinfunction "IO12_14") (pintype "bidirectional"))
      (node (ref "J8") (pin "20") (pinfunction "20_20") (pintype "passive"))
    )
    (net (code "59") (name "4IO13") (class "Default")
      (node (ref "IC3") (pin "16") (pinfunction "IO13_16") (pintype "bidirectional"))
      (node (ref "IC3") (pin "40") (pinfunction "IO13_40") (pintype "bidirectional"))
      (node (ref "J8") (pin "21") (pinfunction "21_21") (pintype "passive"))
    )
    (net (code "60") (name "4IO14") (class "Default")
      (node (ref "IC3") (pin "13") (pinfunction "IO14_13") (pintype "bidirectional"))
      (node (ref "J8") (pin "22") (pinfunction "22_22") (pintype "passive"))
    )
    (net (code "61") (name "4IO15") (class "Default")
      (node (ref "IC3") (pin "23") (pinfunction "IO15_23") (pintype "bidirectional"))
      (node (ref "IC3") (pin "47") (pinfunction "IO15_47") (pintype "bidirectional"))
      (node (ref "J8") (pin "23") (pinfunction "23_23") (pintype "passive"))
    )
    (net (code "62") (name "4IO16") (class "Default")
      (node (ref "IC3") (pin "27") (pinfunction "I16_27") (pintype "bidirectional"))
    )
    (net (code "63") (name "4IO17") (class "Default")
      (node (ref "IC3") (pin "28") (pinfunction "I17_28") (pintype "bidirectional"))
    )
    (net (code "64") (name "4IO18") (class "Default")
      (node (ref "IC3") (pin "30") (pinfunction "IO18_30") (pintype "bidirectional"))
      (node (ref "J8") (pin "15") (pinfunction "15_15") (pintype "passive"))
    )
    (net (code "65") (name "4IO19") (class "Default")
      (node (ref "IC3") (pin "31") (pinfunction "IO19_31") (pintype "bidirectional"))
      (node (ref "J8") (pin "16") (pinfunction "16_16") (pintype "passive"))
    )
    (net (code "66") (name "4IO21") (class "Default")
      (node (ref "IC3") (pin "33") (pinfunction "IO21_33") (pintype "bidirectional"))
      (node (ref "J8") (pin "9") (pinfunction "9_9") (pintype "passive"))
    )
    (net (code "67") (name "4IO22") (class "Default")
      (node (ref "IC3") (pin "36") (pinfunction "IO22_36") (pintype "bidirectional"))
      (node (ref "J8") (pin "10") (pinfunction "10_10") (pintype "passive"))
    )
    (net (code "68") (name "4IO23") (class "Default")
      (node (ref "IC3") (pin "37") (pinfunction "IO23_37") (pintype "bidirectional"))
      (node (ref "J8") (pin "24") (pinfunction "24_24") (pintype "passive"))
    )
    (net (code "69") (name "4IO25") (class "Default")
      (node (ref "IC3") (pin "10") (pinfunction "IO25_10") (pintype "bidirectional"))
      (node (ref "J8") (pin "17") (pinfunction "17_17") (pintype "passive"))
    )
    (net (code "70") (name "4IO26") (class "Default")
      (node (ref "IC3") (pin "11") (pinfunction "IO26_11") (pintype "bidirectional"))
      (node (ref "J8") (pin "13") (pinfunction "13_13") (pintype "passive"))
    )
    (net (code "71") (name "4IO27") (class "Default")
      (node (ref "IC3") (pin "12") (pinfunction "IO27_12") (pintype "bidirectional"))
      (node (ref "J8") (pin "25") (pinfunction "25_25") (pintype "passive"))
    )
    (net (code "72") (name "4IO32") (class "Default")
      (node (ref "IC3") (pin "8") (pinfunction "IO32_8") (pintype "bidirectional"))
      (node (ref "J8") (pin "26") (pinfunction "26_26") (pintype "passive"))
    )
    (net (code "73") (name "4IO33") (class "Default")
      (node (ref "IC3") (pin "9") (pinfunction "IO33_9") (pintype "bidirectional"))
      (node (ref "J8") (pin "18") (pinfunction "18_18") (pintype "passive"))
    )
    (net (code "74") (name "4IO34") (class "Default")
      (node (ref "IC3") (pin "6") (pinfunction "IO34_6") (pintype "bidirectional"))
      (node (ref "J8") (pin "8") (pinfunction "8_8") (pintype "passive"))
    )
    (net (code "75") (name "4IO35") (class "Default")
      (node (ref "IC3") (pin "7") (pinfunction "IO35_7") (pintype "bidirectional"))
      (node (ref "J8") (pin "11") (pinfunction "11_11") (pintype "passive"))
    )
    (net (code "76") (name "4RX0") (class "Default")
      (node (ref "IC3") (pin "34") (pinfunction "RXD0_34") (pintype "input"))
      (node (ref "J7") (pin "5") (pinfunction "5_5") (pintype "passive"))
    )
    (net (code "77") (name "4SVN") (class "Default")
      (node (ref "IC3") (pin "5") (pinfunction "SENSOR_VN_5") (pintype "input"))
      (node (ref "J8") (pin "7") (pinfunction "7_7") (pintype "passive"))
    )
    (net (code "78") (name "4SVP") (class "Default")
      (node (ref "IC3") (pin "4") (pinfunction "SENSOR_VP_4") (pintype "input"))
      (node (ref "J8") (pin "5") (pinfunction "5_5") (pintype "passive"))
    )
    (net (code "79") (name "4TX0") (class "Default")
      (node (ref "IC3") (pin "35") (pinfunction "TXD0_35") (pintype "output"))
      (node (ref "J7") (pin "3") (pinfunction "3_3") (pintype "passive"))
    )
    (net (code "80") (name "GND") (class "Default")
      (node (ref "C1") (pin "2") (pinfunction "2_2") (pintype "passive"))
      (node (ref "C10") (pin "2") (pinfunction "2_2") (pintype "passive"))
      (node (ref "C11") (pin "1") (pinfunction "1_1") (pintype "passive"))
      (node (ref "C12") (pin "2") (pinfunction "-_2") (pintype "passive"))
      (node (ref "C13") (pin "2") (pinfunction "2_2") (pintype "passive"))
      (node (ref "C14") (pin "2") (pinfunction "2_2") (pintype "passive"))
      (node (ref "C15") (pin "2") (pinfunction "-_2") (pintype "passive"))
      (node (ref "C16") (pin "1") (pinfunction "1_1") (pintype "passive"))
      (node (ref "C17") (pin "2") (pinfunction "2_2") (pintype "passive"))
      (node (ref "C2") (pin "2") (pinfunction "-_2") (pintype "passive"))
      (node (ref "C3") (pin "1") (pinfunction "1_1") (pintype "passive"))
      (node (ref "C4") (pin "2") (pinfunction "-_2") (pintype "passive"))
      (node (ref "C5") (pin "1") (pinfunction "1_1") (pintype "passive"))
      (node (ref "C6") (pin "2") (pinfunction "-_2") (pintype "passive"))
      (node (ref "C7") (pin "1") (pinfunction "1_1") (pintype "passive"))
      (node (ref "C8") (pin "2") (pinfunction "-_2") (pintype "passive"))
      (node (ref "C9") (pin "2") (pinfunction "2_2") (pintype "passive"))
      (node (ref "IC1") (pin "GND") (pinfunction "GND_GND") (pintype "power_in"))
      (node (ref "IC2") (pin "GND") (pinfunction "GND_GND") (pintype "bidirectional"))
      (node (ref "IC3") (pin "1") (pinfunction "GND_1") (pintype "power_in"))
      (node (ref "IC3") (pin "15") (pinfunction "GND_15") (pintype "power_in"))
      (node (ref "IC3") (pin "38") (pinfunction "GND_38") (pintype "power_in"))
      (node (ref "IC3") (pin "39") (pinfunction "GND_39") (pintype "power_in"))
      (node (ref "IC3") (pin "GND") (pinfunction "GND_GND") (pintype "power_in"))
      (node (ref "IC3") (pin "PAD$1") (pinfunction "GND_PAD$1") (pintype "power_in"))
      (node (ref "IC3") (pin "PAD$4") (pinfunction "GND_PAD$4") (pintype "power_in"))
      (node (ref "IC3") (pin "PAD$5") (pinfunction "GND_PAD$5") (pintype "power_in"))
      (node (ref "IC3") (pin "PAD$7") (pinfunction "GND_PAD$7") (pintype "power_in"))
      (node (ref "IC3") (pin "PAD$8") (pinfunction "GND_PAD$8") (pintype "power_in"))
      (node (ref "IC3") (pin "PAD$9") (pinfunction "GND_PAD$9") (pintype "power_in"))
      (node (ref "IC4") (pin "P$2") (pinfunction "GND_P$2") (pintype "bidirectional"))
      (node (ref "IC5") (pin "GND") (pinfunction "GND_GND") (pintype "power_in"))
      (node (ref "IC5") (pin "GND1") (pinfunction "GND1_GND1") (pintype "power_in"))
      (node (ref "J1") (pin "4") (pinfunction "4_4") (pintype "passive"))
      (node (ref "J11") (pin "1") (pinfunction "1_1") (pintype "passive"))
      (node (ref "J14") (pin "3") (pinfunction "3_3") (pintype "passive"))
      (node (ref "J15") (pin "3") (pinfunction "S_3") (pintype "passive"))
      (node (ref "J16") (pin "4") (pinfunction "4_4") (pintype "bidirectional"))
      (node (ref "J2") (pin "3") (pinfunction "3_3") (pintype "passive"))
      (node (ref "J3") (pin "GND") (pinfunction "GND_GND") (pintype "power_in"))
      (node (ref "J3") (pin "SH@1") (pinfunction "SHIELD_SH@1") (pintype "bidirectional"))
      (node (ref "J3") (pin "SH@2") (pinfunction "SHIELD_SH@2") (pintype "bidirectional"))
      (node (ref "J3") (pin "SH@3") (pinfunction "SHIELD_SH@3") (pintype "bidirectional"))
      (node (ref "J3") (pin "SH@4") (pinfunction "SHIELD_SH@4") (pintype "bidirectional"))
      (node (ref "J3") (pin "SH@5") (pinfunction "SHIELD_SH@5") (pintype "bidirectional"))
      (node (ref "J3") (pin "SH@6") (pinfunction "SHIELD_SH@6") (pintype "bidirectional"))
      (node (ref "J4") (pin "3") (pinfunction "3_3") (pintype "passive"))
      (node (ref "J5") (pin "GND") (pinfunction "GND_GND") (pintype "power_in"))
      (node (ref "J5") (pin "SH@1") (pinfunction "SHIELD_SH@1") (pintype "bidirectional"))
      (node (ref "J5") (pin "SH@2") (pinfunction "SHIELD_SH@2") (pintype "bidirectional"))
      (node (ref "J5") (pin "SH@3") (pinfunction "SHIELD_SH@3") (pintype "bidirectional"))
      (node (ref "J5") (pin "SH@4") (pinfunction "SHIELD_SH@4") (pintype "bidirectional"))
      (node (ref "J5") (pin "SH@5") (pinfunction "SHIELD_SH@5") (pintype "bidirectional"))
      (node (ref "J5") (pin "SH@6") (pinfunction "SHIELD_SH@6") (pintype "bidirectional"))
      (node (ref "J6") (pin "4") (pinfunction "4_4") (pintype "passive"))
      (node (ref "J7") (pin "4") (pinfunction "4_4") (pintype "passive"))
      (node (ref "J8") (pin "3") (pinfunction "3_3") (pintype "passive"))
      (node (ref "J9") (pin "GND") (pinfunction "GND_GND") (pintype "power_in"))
      (node (ref "J9") (pin "SH@1") (pinfunction "SHIELD_SH@1") (pintype "bidirectional"))
      (node (ref "J9") (pin "SH@2") (pinfunction "SHIELD_SH@2") (pintype "bidirectional"))
      (node (ref "J9") (pin "SH@3") (pinfunction "SHIELD_SH@3") (pintype "bidirectional"))
      (node (ref "J9") (pin "SH@4") (pinfunction "SHIELD_SH@4") (pintype "bidirectional"))
      (node (ref "J9") (pin "SH@5") (pinfunction "SHIELD_SH@5") (pintype "bidirectional"))
      (node (ref "J9") (pin "SH@6") (pinfunction "SHIELD_SH@6") (pintype "bidirectional"))
      (node (ref "R11") (pin "1") (pinfunction "1_1") (pintype "passive"))
      (node (ref "R15") (pin "2") (pinfunction "2_2") (pintype "passive"))
      (node (ref "R3") (pin "2") (pinfunction "2_2") (pintype "passive"))
      (node (ref "SW1") (pin "A") (pinfunction "A_A") (pintype "passive"))
      (node (ref "SW1") (pin "SH0") (pinfunction "SH_SH0") (pintype "power_in"))
      (node (ref "SW2") (pin "A") (pinfunction "A_A") (pintype "passive"))
      (node (ref "SW2") (pin "SH0") (pinfunction "SH_SH0") (pintype "power_in"))
      (node (ref "SW3") (pin "A") (pinfunction "A_A") (pintype "passive"))
      (node (ref "SW3") (pin "SH0") (pinfunction "SH_SH0") (pintype "power_in"))
      (node (ref "SW4") (pin "A") (pinfunction "A_A") (pintype "passive"))
      (node (ref "SW4") (pin "SH0") (pinfunction "SH_SH0") (pintype "power_in"))
      (node (ref "SW5") (pin "A") (pinfunction "A_A") (pintype "passive"))
      (node (ref "SW5") (pin "SH0") (pinfunction "SH_SH0") (pintype "power_in"))
      (node (ref "SW6") (pin "A") (pinfunction "A_A") (pintype "passive"))
      (node (ref "SW6") (pin "SH0") (pinfunction "SH_SH0") (pintype "power_in"))
      (node (ref "SW7") (pin "A") (pinfunction "A_A") (pintype "passive"))
      (node (ref "SW7") (pin "SH0") (pinfunction "SH_SH0") (pintype "power_in"))
      (node (ref "T1") (pin "E") (pinfunction "E_E") (pintype "passive"))
      (node (ref "T2") (pin "E") (pinfunction "E_E") (pintype "passive"))
      (node (ref "U1") (pin "2") (pinfunction "GND_2") (pintype "input"))
      (node (ref "U2") (pin "2") (pinfunction "GND_2") (pintype "input"))
      (node (ref "U3") (pin "2") (pinfunction "GND_2") (pintype "input"))
    )
    (net (code "81") (name "Net-(C17-Pad1)") (class "Default")
      (node (ref "C17") (pin "1") (pinfunction "1_1") (pintype "passive"))
      (node (ref "IC5") (pin "VCC") (pinfunction "VCC_VCC") (pintype "power_in"))
      (node (ref "R16") (pin "1") (pinfunction "1_1") (pintype "passive"))
    )
    (net (code "82") (name "Net-(IC2-PadCH_PD)") (class "Default")
      (node (ref "IC2") (pin "CH_PD") (pinfunction "CH_PD_CH_PD") (pintype "bidirectional"))
      (node (ref "R4") (pin "1") (pinfunction "1_1") (pintype "passive"))
    )
    (net (code "83") (name "Net-(J4-Pad8)") (class "Default")
      (node (ref "J4") (pin "8") (pinfunction "8_8") (pintype "passive"))
      (node (ref "SJ2") (pin "1") (pinfunction "1_1") (pintype "passive"))
    )
    (net (code "84") (name "Net-(J10-Pad1)") (class "Default")
      (node (ref "J10") (pin "1") (pinfunction "1_1") (pintype "passive"))
      (node (ref "K1") (pin "COM") (pinfunction "COM_COM") (pintype "passive"))
    )
    (net (code "85") (name "Net-(J10-Pad2)") (class "Default")
      (node (ref "J10") (pin "2") (pinfunction "2_2") (pintype "passive"))
      (node (ref "J12") (pin "2") (pinfunction "2_2") (pintype "passive"))
      (node (ref "J13") (pin "2") (pinfunction "2_2") (pintype "passive"))
    )
    (net (code "86") (name "Net-(J12-Pad1)") (class "Default")
      (node (ref "J12") (pin "1") (pinfunction "1_1") (pintype "passive"))
      (node (ref "K1") (pin "NO") (pinfunction "NO_NO") (pintype "passive"))
      (node (ref "K2") (pin "NO") (pinfunction "NO_NO") (pintype "passive"))
    )
    (net (code "87") (name "Net-(J13-Pad1)") (class "Default")
      (node (ref "J13") (pin "1") (pinfunction "1_1") (pintype "passive"))
      (node (ref "K2") (pin "COM") (pinfunction "COM_COM") (pintype "passive"))
    )
    (net (code "88") (name "Net-(K1A-1)") (class "Default")
      (node (ref "D1") (pin "A") (pinfunction "A_A") (pintype "passive"))
      (node (ref "K1") (pin "R1") (pinfunction "1_R1") (pintype "passive"))
      (node (ref "T1") (pin "C") (pinfunction "C_C") (pintype "passive"))
    )
    (net (code "89") (name "Net-(K2A-1)") (class "Default")
      (node (ref "D2") (pin "A") (pinfunction "A_A") (pintype "passive"))
      (node (ref "K2") (pin "R1") (pinfunction "1_R1") (pintype "passive"))
      (node (ref "T2") (pin "C") (pinfunction "C_C") (pintype "passive"))
    )
    (net (code "90") (name "Net-(R10-Pad1)") (class "Default")
      (node (ref "R10") (pin "1") (pinfunction "1_1") (pintype "passive"))
      (node (ref "R11") (pin "2") (pinfunction "2_2") (pintype "passive"))
      (node (ref "T1") (pin "B") (pinfunction "B_B") (pintype "passive"))
    )
    (net (code "91") (name "Net-(R13-Pad2)") (class "Default")
      (node (ref "R13") (pin "2") (pinfunction "2_2") (pintype "passive"))
      (node (ref "R15") (pin "1") (pinfunction "1_1") (pintype "passive"))
      (node (ref "T2") (pin "B") (pinfunction "B_B") (pintype "passive"))
    )
    (net (code "92") (name "Net-(R14-P$2)") (class "Default")
      (node (ref "R12") (pin "2") (pinfunction "2_2") (pintype "passive"))
      (node (ref "R14") (pin "2") (pinfunction "P$2_2") (pintype "bidirectional"))
    )
    (net (code "93") (name "Net-(U1-EN)") (class "Default")
      (node (ref "R2") (pin "2") (pinfunction "2_2") (pintype "passive"))
      (node (ref "U1") (pin "3") (pinfunction "EN_3") (pintype "input"))
    )
    (net (code "94") (name "Net-(U2-EN)") (class "Default")
      (node (ref "R7") (pin "2") (pinfunction "2_2") (pintype "passive"))
      (node (ref "U2") (pin "3") (pinfunction "EN_3") (pintype "input"))
    )
    (net (code "95") (name "Net-(U3-EN)") (class "Default")
      (node (ref "R8") (pin "2") (pinfunction "2_2") (pintype "passive"))
      (node (ref "U3") (pin "3") (pinfunction "EN_3") (pintype "input"))
    )
    (net (code "96") (name "unconnected-(IC3-CLK-Pad20)") (class "Default")
      (node (ref "IC3") (pin "20") (pinfunction "CLK_20") (pintype "no_connect"))
    )
    (net (code "97") (name "unconnected-(IC3-CLK-Pad44)") (class "Default")
      (node (ref "IC3") (pin "44") (pinfunction "CLK_44") (pintype "no_connect"))
    )
    (net (code "98") (name "unconnected-(IC3-CMD-Pad19)") (class "Default")
      (node (ref "IC3") (pin "19") (pinfunction "CMD_19") (pintype "no_connect"))
    )
    (net (code "99") (name "unconnected-(IC3-CMD-Pad43)") (class "Default")
      (node (ref "IC3") (pin "43") (pinfunction "CMD_43") (pintype "no_connect"))
    )
    (net (code "100") (name "unconnected-(IC3-NC-Pad32)") (class "Default")
      (node (ref "IC3") (pin "32") (pinfunction "NC_32") (pintype "no_connect"))
    )
    (net (code "101") (name "unconnected-(IC3-SD0-Pad21)") (class "Default")
      (node (ref "IC3") (pin "21") (pinfunction "SD0_21") (pintype "no_connect"))
    )
    (net (code "102") (name "unconnected-(IC3-SD0-Pad45)") (class "Default")
      (node (ref "IC3") (pin "45") (pinfunction "SD0_45") (pintype "no_connect"))
    )
    (net (code "103") (name "unconnected-(IC3-SD1-Pad22)") (class "Default")
      (node (ref "IC3") (pin "22") (pinfunction "SD1_22") (pintype "no_connect"))
    )
    (net (code "104") (name "unconnected-(IC3-SD1-Pad46)") (class "Default")
      (node (ref "IC3") (pin "46") (pinfunction "SD1_46") (pintype "no_connect"))
    )
    (net (code "105") (name "unconnected-(IC3-SD2-Pad17)") (class "Default")
      (node (ref "IC3") (pin "17") (pinfunction "SD2_17") (pintype "no_connect"))
    )
    (net (code "106") (name "unconnected-(IC3-SD2-Pad41)") (class "Default")
      (node (ref "IC3") (pin "41") (pinfunction "SD2_41") (pintype "no_connect"))
    )
    (net (code "107") (name "unconnected-(IC3-SD3-Pad18)") (class "Default")
      (node (ref "IC3") (pin "18") (pinfunction "SD3_18") (pintype "no_connect"))
    )
    (net (code "108") (name "unconnected-(IC3-SD3-Pad42)") (class "Default")
      (node (ref "IC3") (pin "42") (pinfunction "SD3_42") (pintype "no_connect"))
    )
    (net (code "109") (name "unconnected-(J3-PadID)") (class "Default")
      (node (ref "J3") (pin "ID") (pinfunction "ID_ID") (pintype "bidirectional"))
    )
    (net (code "110") (name "unconnected-(J5-PadD+)") (class "Default")
      (node (ref "J5") (pin "D+") (pinfunction "D+_D+") (pintype "bidirectional"))
    )
    (net (code "111") (name "unconnected-(J5-PadD-)") (class "Default")
      (node (ref "J5") (pin "D-") (pinfunction "D-_D-") (pintype "bidirectional"))
    )
    (net (code "112") (name "unconnected-(J5-PadID)") (class "Default")
      (node (ref "J5") (pin "ID") (pinfunction "ID_ID") (pintype "bidirectional"))
    )
    (net (code "113") (name "unconnected-(J9-PadD+)") (class "Default")
      (node (ref "J9") (pin "D+") (pinfunction "D+_D+") (pintype "bidirectional"))
    )
    (net (code "114") (name "unconnected-(J9-PadD-)") (class "Default")
      (node (ref "J9") (pin "D-") (pinfunction "D-_D-") (pintype "bidirectional"))
    )
    (net (code "115") (name "unconnected-(J9-PadID)") (class "Default")
      (node (ref "J9") (pin "ID") (pinfunction "ID_ID") (pintype "bidirectional"))
    )
    (net (code "116") (name "unconnected-(J14-Pad11)") (class "Default")
      (node (ref "J14") (pin "11") (pinfunction "11_11") (pintype "passive"))
    )
    (net (code "117") (name "unconnected-(J14-Pad13)") (class "Default")
      (node (ref "J14") (pin "13") (pinfunction "13_13") (pintype "passive"))
    )
    (net (code "118") (name "unconnected-(K1-PadNC)") (class "Default")
      (node (ref "K1") (pin "NC") (pinfunction "NC_NC") (pintype "passive"))
    )
    (net (code "119") (name "unconnected-(K2-PadNC)") (class "Default")
      (node (ref "K2") (pin "NC") (pinfunction "NC_NC") (pintype "passive"))
    )
    (net (code "120") (name "unconnected-(U1-BP-Pad4)") (class "Default")
      (node (ref "U1") (pin "4") (pinfunction "BP_4") (pintype "input"))
    )
    (net (code "121") (name "unconnected-(U2-BP-Pad4)") (class "Default")
      (node (ref "U2") (pin "4") (pinfunction "BP_4") (pintype "input"))
    )
    (net (code "122") (name "unconnected-(U3-BP-Pad4)") (class "Default")
      (node (ref "U3") (pin "4") (pinfunction "BP_4") (pintype "input"))
    )
  )
)
